# ultrasonic_tank_monitor.net
KiCad netlist of a schematic drawn in Altium Designer
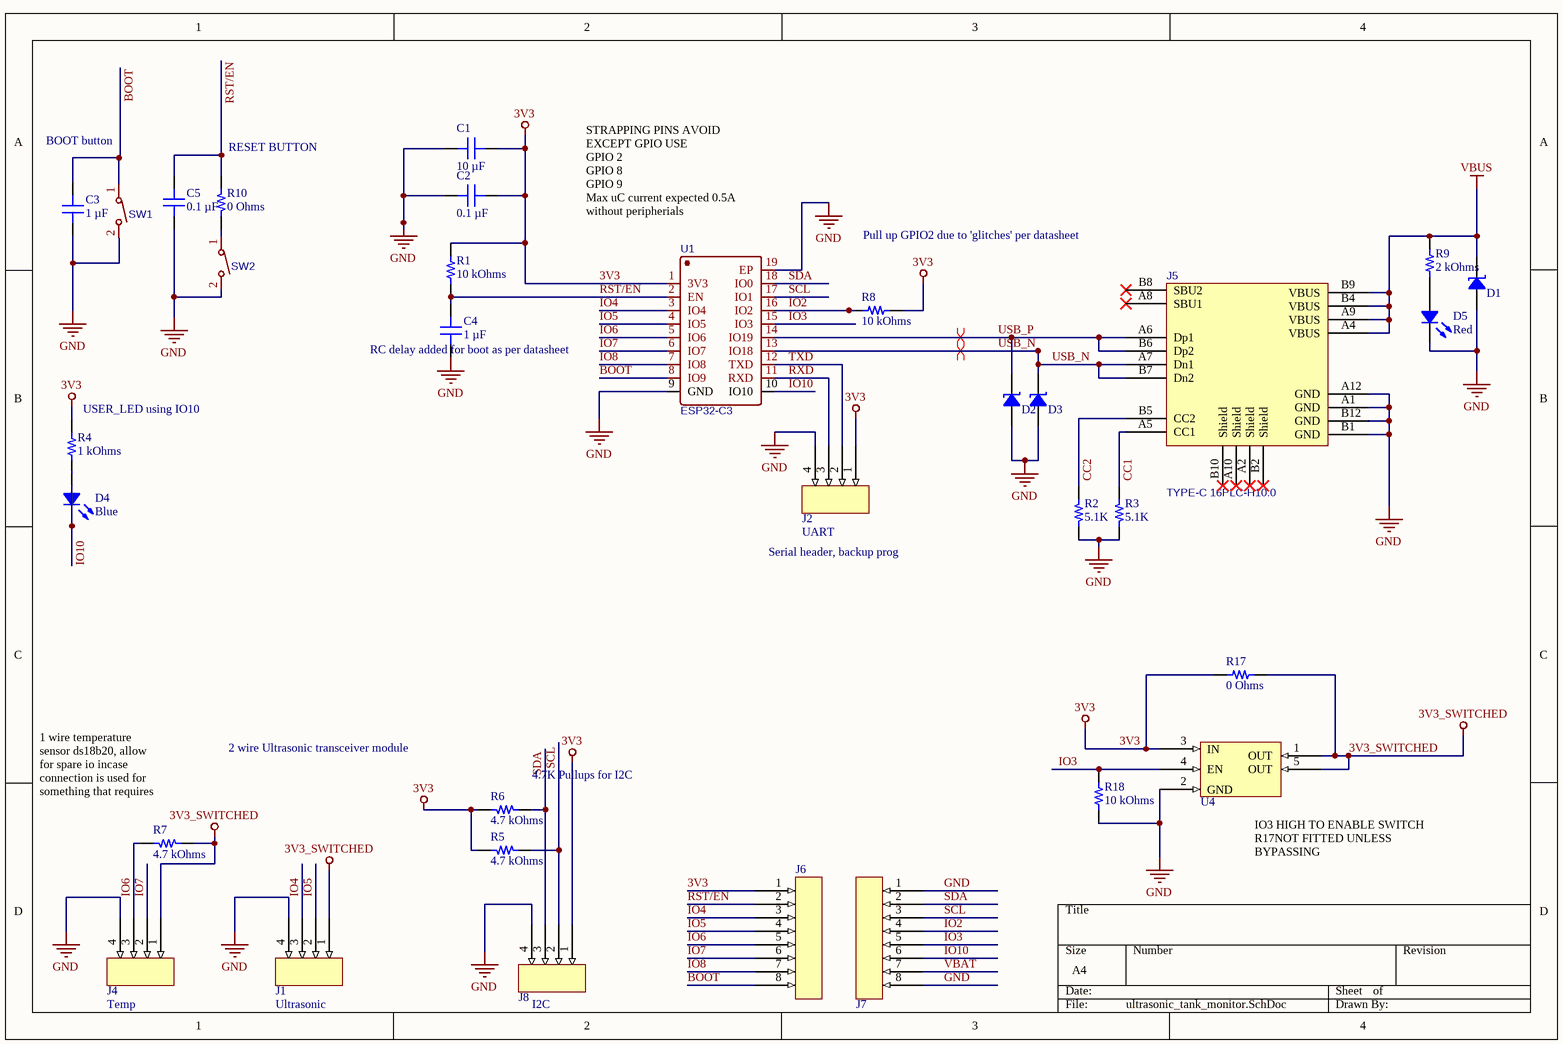
[diagram p0: ultrasonic_tank_monitor.SchDoc]

(export (version "E")
  (design (tool "Eeschema 10.0.6"))
  (components
    (comp (ref "C1")
      (value "10 µF")
      (footprint "CAP 0603_1608")
      (description "CAP CER 10UF 10V X5R 0603")
      (fields
        (field (name "PART NUMBER") "GRM188R61A106ME69D")
        (field (name "MANUFACTURER") "Murata Electronics")
      )
      (libsource (lib "Celestial Altium Library - altium_library") (part "Capacitor"))
    )
    (comp (ref "C2")
      (value "0.1 µF")
      (footprint "CAP 0603_1608")
      (description "CAP CER 0.1UF 10V X7R 0603")
      (fields
        (field (name "PART NUMBER") "VJ0603Y104MXQCW1BC")
        (field (name "MANUFACTURER") "Vishay Vitramon")
      )
      (libsource (lib "Celestial Altium Library - altium_library") (part "Capacitor"))
    )
    (comp (ref "C3")
      (value "1 µF")
      (footprint "CAP 0603_1608")
      (description "CAP CER 1UF 10V X7R 0603")
      (fields (field (name "PART NUMBER") "LMK107B7105KAHT") (field (name "MANUFACTURER") "Taiyo Yuden"))
      (libsource (lib "Celestial Altium Library - altium_library") (part "Capacitor"))
    )
    (comp (ref "C4")
      (value "1 µF")
      (footprint "CAP 0603_1608")
      (description "CAP CER 1UF 10V X7R 0603")
      (fields (field (name "PART NUMBER") "LMK107B7105KAHT") (field (name "MANUFACTURER") "Taiyo Yuden"))
      (libsource (lib "Celestial Altium Library - altium_library") (part "Capacitor"))
    )
    (comp (ref "C5")
      (value "0.1 µF")
      (footprint "CAP 0603_1608")
      (description "CAP CER 0.1UF 10V X7R 0603")
      (fields
        (field (name "PART NUMBER") "VJ0603Y104MXQCW1BC")
        (field (name "MANUFACTURER") "Vishay Vitramon")
      )
      (libsource (lib "Celestial Altium Library - altium_library") (part "Capacitor"))
    )
    (comp (ref "D1")
      (value "VESD16C1-02V-G3-08")
      (footprint "SOD523F")
      (description "ESD PROTECTION DIODE SOD-523")
      (fields (field (name "MANUFACTURER") "Vishay Semiconductor Diodes Division"))
      (libsource (lib "Celestial Altium Library - altium_library") (part "DIODE TVS UNI"))
    )
    (comp (ref "D2")
      (value "VESD16C1-02V-G3-08")
      (footprint "SOD523F")
      (description "ESD PROTECTION DIODE SOD-523")
      (fields (field (name "MANUFACTURER") "Vishay Semiconductor Diodes Division"))
      (libsource (lib "Celestial Altium Library - altium_library") (part "DIODE TVS UNI"))
    )
    (comp (ref "D3")
      (value "VESD16C1-02V-G3-08")
      (footprint "SOD523F")
      (description "ESD PROTECTION DIODE SOD-523")
      (fields (field (name "MANUFACTURER") "Vishay Semiconductor Diodes Division"))
      (libsource (lib "Celestial Altium Library - altium_library") (part "DIODE TVS UNI"))
    )
    (comp (ref "D4")
      (value "Blue")
      (footprint "LED 0805_2012 BLUE")
      (description "LED BLUE 0805 SMD")
      (fields (field (name "PART NUMBER") "5973605607F") (field (name "MANUFACTURER") "Dialight"))
      (libsource (lib "Celestial Altium Library - altium_library") (part "LED"))
    )
    (comp (ref "D5")
      (value "Red")
      (footprint "LED 0805_2012 RED")
      (description "LED RED 0805 SMD")
      (fields (field (name "PART NUMBER") "5990110007F") (field (name "MANUFACTURER") "Dialight"))
      (libsource (lib "Celestial Altium Library - altium_library") (part "LED"))
    )
    (comp (ref "J1")
      (value "Ultrasonic")
      (footprint "HDR-TH_4P-P2.54-V-M")
      (libsource (lib "Pidgeon_SCH") (part "HDR-TH_4P-P2.54"))
    )
    (comp (ref "J2")
      (value "UART")
      (footprint "HDR-TH_4P-P2.54-V-M")
      (libsource (lib "Pidgeon_SCH") (part "HDR-TH_4P-P2.54"))
    )
    (comp (ref "J4")
      (value "Temp")
      (footprint "HDR-TH_4P-P2.54-V-M")
      (libsource (lib "Pidgeon_SCH") (part "HDR-TH_4P-P2.54"))
    )
    (comp (ref "J5")
      (value "TYPE-C 16PLC-H10.0")
      (footprint "TYPE-C-TH_16PLC-H10.0")
      (fields (field (name "MANUFACTURER") "SHOU HAN(首韩)") (field (name "CONTRIBUTOR") "lcsc"))
      (libsource (lib "Pidgeon_SCH") (part "TYPE-C 16PLC-H10.0"))
    )
    (comp (ref "J6")
      (value "HDR-TH_8P-P2.54")
      (footprint "HDR-TH_8P-P2.54-V-M")
      (libsource (lib "") (part "HDR-TH_8P-P2.54_1"))
    )
    (comp (ref "J7")
      (value "HDR-TH_8P-P2.54")
      (footprint "HDR-TH_8P-P2.54-V-M")
      (libsource (lib "Pidgeon_SCH") (part "HDR-TH_8P-P2.54"))
    )
    (comp (ref "J8")
      (value "I2C")
      (footprint "HDR-TH_4P-P2.54-V-M")
      (libsource (lib "Pidgeon_SCH") (part "HDR-TH_4P-P2.54"))
    )
    (comp (ref "R1")
      (value "10 kOhms")
      (footprint "RES 0603_1608")
      (description "RES SMD 10K OHM 5% 1/10W 0603")
      (fields (field (name "PART NUMBER") "CRCW060310K0JNEB") (field (name "MANUFACTURER") "Vishay Dale"))
      (libsource (lib "Celestial Altium Library - altium_library") (part "Resistor"))
    )
    (comp (ref "R2")
      (value "5.1K")
      (footprint "RES 0603_1608")
      (description "RES 5.1K OHM 5% 1/10W 0603")
      (fields
        (field (name "PART NUMBER") "RMEF0603JT5K10")
        (field (name "MANUFACTURER") "Stackpole Electronics Inc")
      )
      (libsource (lib "Celestial Altium Library - altium_library") (part "Resistor"))
    )
    (comp (ref "R3")
      (value "5.1K")
      (footprint "RES 0603_1608")
      (description "RES 5.1K OHM 5% 1/10W 0603")
      (fields
        (field (name "PART NUMBER") "RMEF0603JT5K10")
        (field (name "MANUFACTURER") "Stackpole Electronics Inc")
      )
      (libsource (lib "Celestial Altium Library - altium_library") (part "Resistor"))
    )
    (comp (ref "R4")
      (value "1 kOhms")
      (footprint "RES 0603_1608")
      (description "RES 1K OHM 5% 1/10W 0603")
      (fields
        (field (name "PART NUMBER") "WR06X102 JTL")
        (field (name "MANUFACTURER") "Walsin Technology Corporation")
      )
      (libsource (lib "Celestial Altium Library - altium_library") (part "Resistor"))
    )
    (comp (ref "R5")
      (value "4.7 kOhms")
      (footprint "RES 0603_1608")
      (description "RES 4.7K OHM 1% 1/10W 0603")
      (fields
        (field (name "PART NUMBER") "WR06X4701FTL")
        (field (name "MANUFACTURER") "Walsin Technology Corporation")
      )
      (libsource (lib "Celestial Altium Library - altium_library") (part "Resistor"))
    )
    (comp (ref "R6")
      (value "4.7 kOhms")
      (footprint "RES 0603_1608")
      (description "RES 4.7K OHM 1% 1/10W 0603")
      (fields
        (field (name "PART NUMBER") "WR06X4701FTL")
        (field (name "MANUFACTURER") "Walsin Technology Corporation")
      )
      (libsource (lib "Celestial Altium Library - altium_library") (part "Resistor"))
    )
    (comp (ref "R7")
      (value "4.7 kOhms")
      (footprint "RES 0603_1608")
      (description "RES 4.7K OHM 1% 1/10W 0603")
      (fields
        (field (name "PART NUMBER") "WR06X4701FTL")
        (field (name "MANUFACTURER") "Walsin Technology Corporation")
      )
      (libsource (lib "Celestial Altium Library - altium_library") (part "Resistor"))
    )
    (comp (ref "R8")
      (value "10 kOhms")
      (footprint "RES 0603_1608")
      (description "RES SMD 10K OHM 5% 1/10W 0603")
      (fields (field (name "PART NUMBER") "CRCW060310K0JNEB") (field (name "MANUFACTURER") "Vishay Dale"))
      (libsource (lib "Celestial Altium Library - altium_library") (part "Resistor"))
    )
    (comp (ref "R9")
      (value "2 kOhms")
      (footprint "RES 0603_1608")
      (description "RES 2K OHM 5% 1/10W 0603")
      (fields (field (name "PART NUMBER") "RC0603JR-102KL") (field (name "MANUFACTURER") "Yageo"))
      (libsource (lib "Celestial Altium Library - altium_library") (part "Resistor"))
    )
    (comp (ref "R10")
      (value "0 Ohms")
      (footprint "RES 0603_1608")
      (description "RES SMD 0.0 JUMPER 1/10W 0603")
      (fields
        (field (name "PART NUMBER") "WR06X000 PTL")
        (field (name "MANUFACTURER") "Walsin Technology Corporation")
      )
      (libsource (lib "Celestial Altium Library - altium_library") (part "Resistor"))
    )
    (comp (ref "R17")
      (value "0 Ohms")
      (footprint "RES 1206_3216")
      (description "RES SMD 0 OHM 3/4W 1206 WIDE")
      (fields (field (name "PART NUMBER") "RCL06120000Z0EA") (field (name "MANUFACTURER") "Vishay Dale"))
      (libsource (lib "Celestial Altium Library - altium_library") (part "Resistor"))
    )
    (comp (ref "R18")
      (value "10 kOhms")
      (footprint "RES 0603_1608")
      (description "RES SMD 10K OHM 5% 1/10W 0603")
      (fields (field (name "PART NUMBER") "CRCW060310K0JNEB") (field (name "MANUFACTURER") "Vishay Dale"))
      (libsource (lib "Celestial Altium Library - altium_library") (part "Resistor"))
    )
    (comp (ref "SW1")
      (value "TS-1185-B-A-B-A")
      (footprint "SW-SMD_L4.0-W3.0-LS5.0")
      (description "Tactile Switch SMD 4x3x2 50mA")
      (fields (field (name "MANUFACTURER") "XKB Connectivity(中国星坤)") (field (name "CONTRIBUTOR") "LCSC"))
      (libsource (lib "Pidgeon_SCH") (part "TS-1185-B-A-B-A"))
    )
    (comp (ref "SW2")
      (value "TS-1185-B-A-B-A")
      (footprint "SW-SMD_L4.0-W3.0-LS5.0")
      (description "Tactile Switch SMD 4x3x2 50mA")
      (fields (field (name "MANUFACTURER") "XKB Connectivity(中国星坤)") (field (name "CONTRIBUTOR") "LCSC"))
      (libsource (lib "Pidgeon_SCH") (part "TS-1185-B-A-B-A"))
    )
    (comp (ref "U1")
      (value "ESP32-C3")
      (footprint "BULETM-SMD_ESPRESSIF_ESP32-C3-WROOM-02-N4-4MB")
      (fields
        (field (name "MANUFACTURER") "ESPRESSIF(乐鑫)")
        (field (name "MANUFACTURER PART") "ESP32-C3-WROOM-02-N4")
        (field (name "CONTRIBUTOR") "LCSC")
      )
      (libsource (lib "Pidgeon_SCH") (part "ESP32-C3-WROOM-02-N4(4MB)"))
    )
    (comp (ref "U4")
      (value "AP22818AKBWT-7")
      (footprint "SOT-23-5_L2.9-W1.6-P0.95-LS2.8-BR")
      (description "High active 2A load distribution switch")
      (libsource (lib "Pidgeon_SCH") (part "AP22818AKBWT-7"))
    )
  )
  (nets
    (net (code "1") (name "/BOOT") (class "Default")
      (node (ref "C3") (pin "2") (pinfunction "2_2") (pintype "passive"))
      (node (ref "J6") (pin "8") (pintype "input"))
      (node (ref "SW1") (pin "1") (pinfunction "1_1") (pintype "passive"))
      (node (ref "U1") (pin "8") (pinfunction "IO9_8") (pintype "passive"))
    )
    (net (code "2") (name "/CC1") (class "Default")
      (node (ref "J5") (pin "A5") (pinfunction "CC1_A5") (pintype "passive"))
      (node (ref "R3") (pin "2") (pinfunction "2_2") (pintype "passive"))
    )
    (net (code "3") (name "/CC2") (class "Default")
      (node (ref "J5") (pin "B5") (pinfunction "CC2_B5") (pintype "passive"))
      (node (ref "R2") (pin "2") (pinfunction "2_2") (pintype "passive"))
    )
    (net (code "4") (name "/IO2") (class "Default")
      (node (ref "J7") (pin "4") (pintype "input"))
      (node (ref "R8") (pin "1") (pinfunction "1_1") (pintype "passive"))
      (node (ref "U1") (pin "16") (pinfunction "IO2_16") (pintype "passive"))
    )
    (net (code "5") (name "/IO3") (class "Default")
      (node (ref "J7") (pin "5") (pintype "input"))
      (node (ref "R18") (pin "1") (pinfunction "1_1") (pintype "passive"))
      (node (ref "U1") (pin "15") (pinfunction "IO3_15") (pintype "passive"))
      (node (ref "U4") (pin "4") (pinfunction "EN_4") (pintype "input"))
    )
    (net (code "6") (name "/IO4") (class "Default")
      (node (ref "J1") (pin "3") (pintype "input"))
      (node (ref "J6") (pin "3") (pintype "input"))
      (node (ref "U1") (pin "3") (pinfunction "IO4_3") (pintype "passive"))
    )
    (net (code "7") (name "/IO5") (class "Default")
      (node (ref "J1") (pin "2") (pintype "input"))
      (node (ref "J6") (pin "4") (pintype "input"))
      (node (ref "U1") (pin "4") (pinfunction "IO5_4") (pintype "passive"))
    )
    (net (code "8") (name "/IO6") (class "Default")
      (node (ref "J4") (pin "3") (pintype "input"))
      (node (ref "J6") (pin "5") (pintype "input"))
      (node (ref "R7") (pin "2") (pinfunction "2_2") (pintype "passive"))
      (node (ref "U1") (pin "5") (pinfunction "IO6_5") (pintype "passive"))
    )
    (net (code "9") (name "/IO7") (class "Default")
      (node (ref "J4") (pin "2") (pintype "input"))
      (node (ref "J6") (pin "6") (pintype "input"))
      (node (ref "U1") (pin "6") (pinfunction "IO7_6") (pintype "passive"))
    )
    (net (code "10") (name "/IO8") (class "Default")
      (node (ref "J6") (pin "7") (pintype "input"))
      (node (ref "U1") (pin "7") (pinfunction "IO8_7") (pintype "passive"))
    )
    (net (code "11") (name "/IO10") (class "Default")
      (node (ref "D4") (pin "2") (pinfunction "2_2") (pintype "passive"))
      (node (ref "J7") (pin "6") (pintype "input"))
      (node (ref "U1") (pin "10") (pinfunction "IO10_10") (pintype "passive"))
    )
    (net (code "12") (name "/RST{slash}EN") (class "Default")
      (node (ref "C4") (pin "2") (pinfunction "2_2") (pintype "passive"))
      (node (ref "C5") (pin "2") (pinfunction "2_2") (pintype "passive"))
      (node (ref "J6") (pin "2") (pintype "input"))
      (node (ref "R1") (pin "2") (pinfunction "2_2") (pintype "passive"))
      (node (ref "R10") (pin "2") (pinfunction "2_2") (pintype "passive"))
      (node (ref "U1") (pin "2") (pinfunction "EN_2") (pintype "passive"))
    )
    (net (code "13") (name "/RXD") (class "Default")
      (node (ref "J2") (pin "3") (pintype "input"))
      (node (ref "U1") (pin "11") (pinfunction "RXD_11") (pintype "passive"))
    )
    (net (code "14") (name "/SCL") (class "Default")
      (node (ref "J7") (pin "3") (pintype "input"))
      (node (ref "J8") (pin "2") (pintype "input"))
      (node (ref "R5") (pin "1") (pinfunction "1_1") (pintype "passive"))
      (node (ref "U1") (pin "17") (pinfunction "IO1_17") (pintype "passive"))
    )
    (net (code "15") (name "/SDA") (class "Default")
      (node (ref "J7") (pin "2") (pintype "input"))
      (node (ref "J8") (pin "3") (pintype "input"))
      (node (ref "R6") (pin "1") (pinfunction "1_1") (pintype "passive"))
      (node (ref "U1") (pin "18") (pinfunction "IO0_18") (pintype "passive"))
    )
    (net (code "16") (name "/TXD") (class "Default")
      (node (ref "J2") (pin "2") (pintype "input"))
      (node (ref "U1") (pin "12") (pinfunction "TXD_12") (pintype "passive"))
    )
    (net (code "17") (name "/USB_N") (class "Default")
      (node (ref "D3") (pin "2") (pinfunction "2_2") (pintype "passive"))
      (node (ref "J5") (pin "A7") (pinfunction "Dn1_A7") (pintype "passive"))
      (node (ref "J5") (pin "B7") (pinfunction "Dn2_B7") (pintype "passive"))
      (node (ref "U1") (pin "13") (pinfunction "IO18_13") (pintype "passive"))
    )
    (net (code "18") (name "/USB_P") (class "Default")
      (node (ref "D2") (pin "2") (pinfunction "2_2") (pintype "passive"))
      (node (ref "J5") (pin "A6") (pinfunction "Dp1_A6") (pintype "passive"))
      (node (ref "J5") (pin "B6") (pinfunction "Dp2_B6") (pintype "passive"))
      (node (ref "U1") (pin "14") (pinfunction "IO19_14") (pintype "passive"))
    )
    (net (code "19") (name "/VBAT") (class "Default") (node (ref "J7") (pin "7") (pintype "input")))
    (net (code "20") (name "3V3") (class "Default")
      (node (ref "C1") (pin "2") (pinfunction "2_2") (pintype "passive"))
      (node (ref "C2") (pin "2") (pinfunction "2_2") (pintype "passive"))
      (node (ref "J2") (pin "1") (pintype "input"))
      (node (ref "J6") (pin "1") (pintype "input"))
      (node (ref "J8") (pin "1") (pintype "input"))
      (node (ref "R1") (pin "1") (pinfunction "1_1") (pintype "passive"))
      (node (ref "R17") (pin "1") (pinfunction "1_1") (pintype "passive"))
      (node (ref "R4") (pin "2") (pinfunction "2_2") (pintype "passive"))
      (node (ref "R5") (pin "2") (pinfunction "2_2") (pintype "passive"))
      (node (ref "R6") (pin "2") (pinfunction "2_2") (pintype "passive"))
      (node (ref "R8") (pin "2") (pinfunction "2_2") (pintype "passive"))
      (node (ref "U1") (pin "1") (pinfunction "3V3_1") (pintype "passive"))
      (node (ref "U4") (pin "3") (pinfunction "IN_3") (pintype "input"))
    )
    (net (code "21") (name "3V3_SWITCHED") (class "Default")
      (node (ref "J1") (pin "1") (pintype "input"))
      (node (ref "J4") (pin "1") (pintype "input"))
      (node (ref "R17") (pin "2") (pinfunction "2_2") (pintype "passive"))
      (node (ref "R7") (pin "1") (pinfunction "1_1") (pintype "passive"))
      (node (ref "U4") (pin "1") (pinfunction "OUT_1") (pintype "input"))
      (node (ref "U4") (pin "5") (pinfunction "OUT_5") (pintype "input"))
    )
    (net (code "22") (name "GND") (class "Default")
      (node (ref "C1") (pin "1") (pinfunction "1_1") (pintype "passive"))
      (node (ref "C2") (pin "1") (pinfunction "1_1") (pintype "passive"))
      (node (ref "C3") (pin "1") (pinfunction "1_1") (pintype "passive"))
      (node (ref "C4") (pin "1") (pinfunction "1_1") (pintype "passive"))
      (node (ref "C5") (pin "1") (pinfunction "1_1") (pintype "passive"))
      (node (ref "D1") (pin "1") (pinfunction "1_1") (pintype "passive"))
      (node (ref "D2") (pin "1") (pinfunction "1_1") (pintype "passive"))
      (node (ref "D3") (pin "1") (pinfunction "1_1") (pintype "passive"))
      (node (ref "D5") (pin "2") (pinfunction "2_2") (pintype "passive"))
      (node (ref "J1") (pin "4") (pintype "input"))
      (node (ref "J2") (pin "4") (pintype "input"))
      (node (ref "J4") (pin "4") (pintype "input"))
      (node (ref "J5") (pin "A1") (pinfunction "GND_A1") (pintype "passive"))
      (node (ref "J5") (pin "A12") (pinfunction "GND_A12") (pintype "passive"))
      (node (ref "J5") (pin "B1") (pinfunction "GND_B1") (pintype "passive"))
      (node (ref "J5") (pin "B12") (pinfunction "GND_B12") (pintype "passive"))
      (node (ref "J7") (pin "1") (pintype "input"))
      (node (ref "J7") (pin "8") (pintype "input"))
      (node (ref "J8") (pin "4") (pintype "input"))
      (node (ref "R18") (pin "2") (pinfunction "2_2") (pintype "passive"))
      (node (ref "R2") (pin "1") (pinfunction "1_1") (pintype "passive"))
      (node (ref "R3") (pin "1") (pinfunction "1_1") (pintype "passive"))
      (node (ref "SW1") (pin "2") (pinfunction "2_2") (pintype "passive"))
      (node (ref "SW2") (pin "2") (pinfunction "2_2") (pintype "passive"))
      (node (ref "U1") (pin "19") (pinfunction "EP_19") (pintype "passive"))
      (node (ref "U1") (pin "9") (pinfunction "GND_9") (pintype "passive"))
      (node (ref "U4") (pin "2") (pinfunction "GND_2") (pintype "input"))
    )
    (net (code "23") (name "Net-(D4-Pad1)") (class "Default")
      (node (ref "D4") (pin "1") (pinfunction "1_1") (pintype "passive"))
      (node (ref "R4") (pin "1") (pinfunction "1_1") (pintype "passive"))
    )
    (net (code "24") (name "Net-(D5-Pad1)") (class "Default")
      (node (ref "D5") (pin "1") (pinfunction "1_1") (pintype "passive"))
      (node (ref "R9") (pin "1") (pinfunction "1_1") (pintype "passive"))
    )
    (net (code "25") (name "Net-(R10-Pad1)") (class "Default")
      (node (ref "R10") (pin "1") (pinfunction "1_1") (pintype "passive"))
      (node (ref "SW2") (pin "1") (pinfunction "1_1") (pintype "passive"))
    )
    (net (code "26") (name "VBUS") (class "Default")
      (node (ref "D1") (pin "2") (pinfunction "2_2") (pintype "passive"))
      (node (ref "J5") (pin "A4") (pinfunction "VBUS_A4") (pintype "passive"))
      (node (ref "J5") (pin "A9") (pinfunction "VBUS_A9") (pintype "passive"))
      (node (ref "J5") (pin "B4") (pinfunction "VBUS_B4") (pintype "passive"))
      (node (ref "J5") (pin "B9") (pinfunction "VBUS_B9") (pintype "passive"))
      (node (ref "R9") (pin "2") (pinfunction "2_2") (pintype "passive"))
    )
    (net (code "27") (name "unconnected-(J5-SBU1-PadA8)") (class "Default")
      (node (ref "J5") (pin "A8") (pinfunction "SBU1_A8") (pintype "passive+no_connect"))
    )
    (net (code "28") (name "unconnected-(J5-SBU2-PadB8)") (class "Default")
      (node (ref "J5") (pin "B8") (pinfunction "SBU2_B8") (pintype "passive+no_connect"))
    )
    (net (code "29") (name "unconnected-(J5-Shield-PadA2)") (class "Default")
      (node (ref "J5") (pin "A2") (pinfunction "Shield_A2") (pintype "passive+no_connect"))
    )
    (net (code "30") (name "unconnected-(J5-Shield-PadA10)") (class "Default")
      (node (ref "J5") (pin "A10") (pinfunction "Shield_A10") (pintype "passive+no_connect"))
    )
    (net (code "31") (name "unconnected-(J5-Shield-PadB2)") (class "Default")
      (node (ref "J5") (pin "B2") (pinfunction "Shield_B2") (pintype "passive+no_connect"))
    )
    (net (code "32") (name "unconnected-(J5-Shield-PadB10)") (class "Default")
      (node (ref "J5") (pin "B10") (pinfunction "Shield_B10") (pintype "passive+no_connect"))
    )
  )
)
